# Project_Zero.net
KiCad netlist of a schematic drawn in EasyEDA Pro
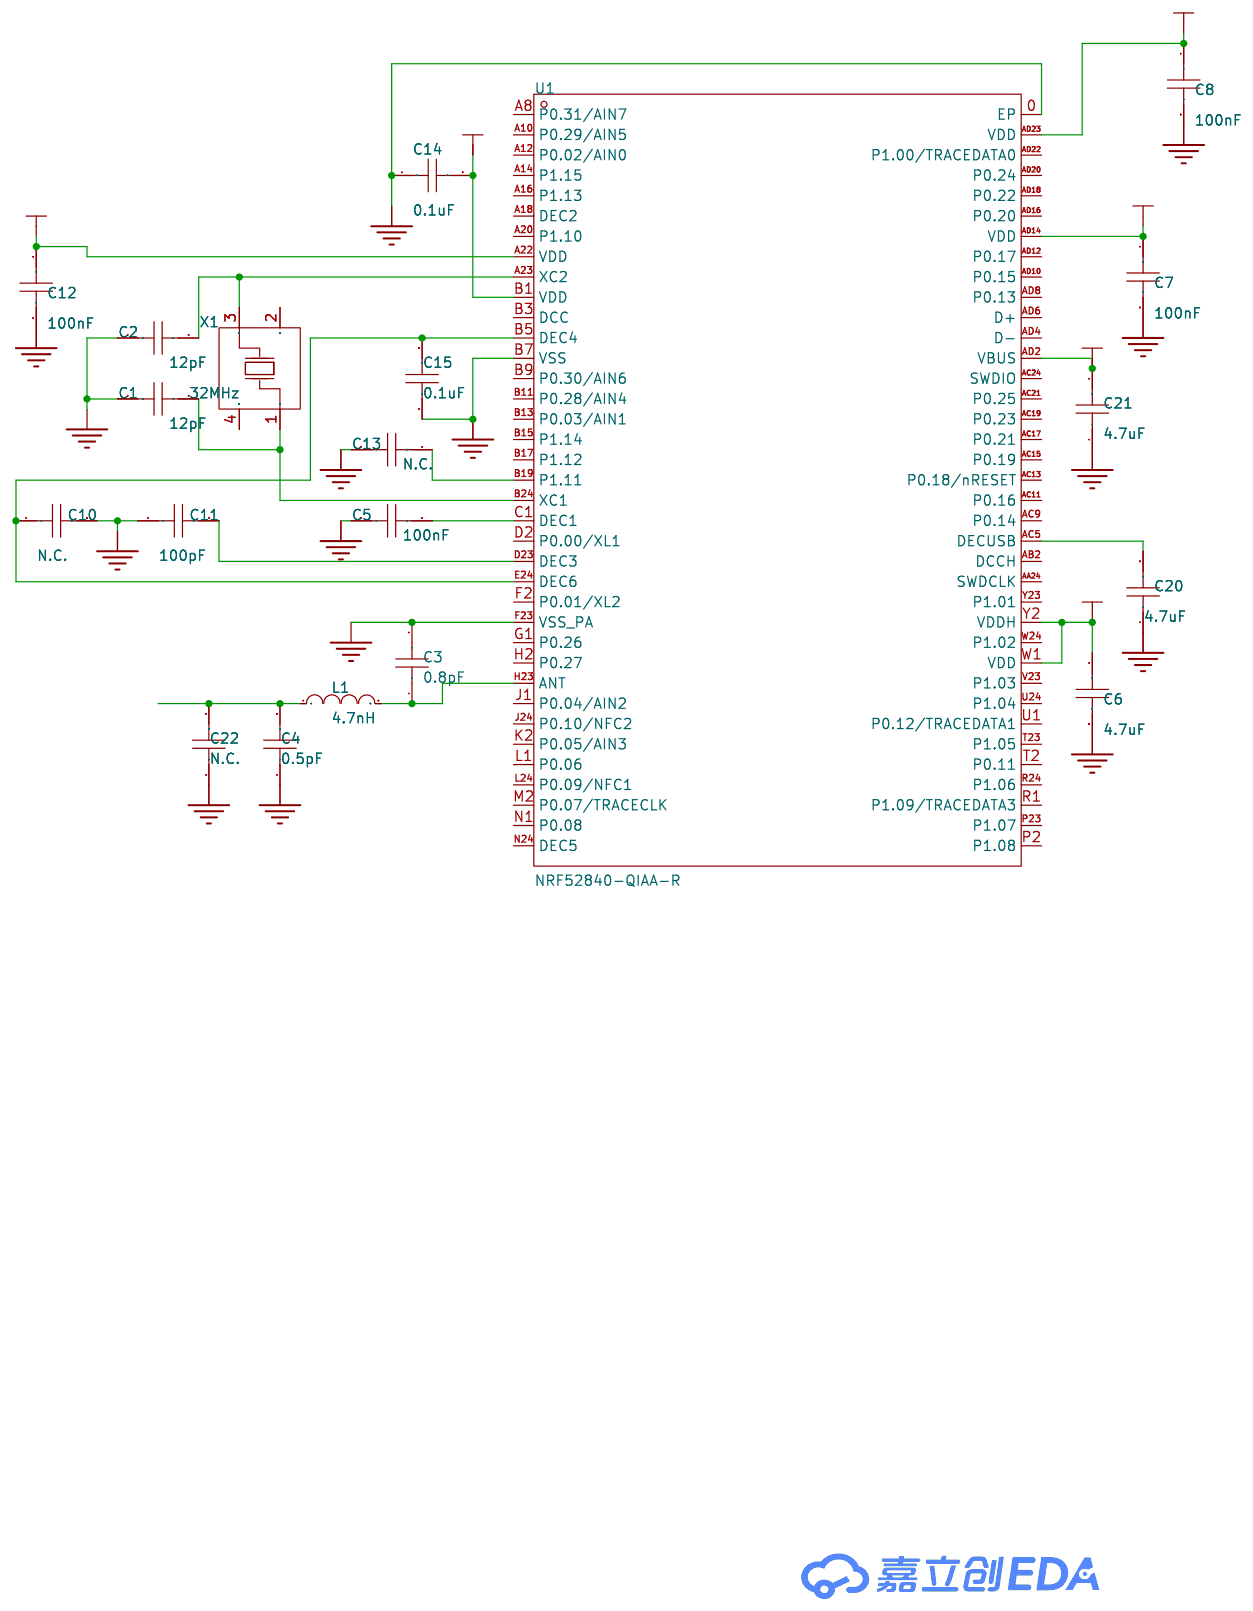
[diagram p0: schematic sheet]

(export (version "E")
  (design (tool "Eeschema 10.0.6"))
  (components
    (comp (ref "C1")
      (value "12pF")
      (footprint "easyedapro:C0603")
      (libsource (lib "easyedapro") (part "CapAcitance"))
    )
    (comp (ref "C2")
      (value "12pF")
      (footprint "easyedapro:C0603")
      (libsource (lib "easyedapro") (part "CapAcitance"))
    )
    (comp (ref "C3")
      (value "0.8pF")
      (footprint "easyedapro:C0603")
      (libsource (lib "easyedapro") (part "CapAcitance"))
    )
    (comp (ref "C4")
      (value "0.5pF")
      (footprint "easyedapro:C0603")
      (libsource (lib "easyedapro") (part "CapAcitance"))
    )
    (comp (ref "C5")
      (value "100nF")
      (footprint "easyedapro:C0603")
      (libsource (lib "easyedapro") (part "CapAcitance"))
    )
    (comp (ref "C6")
      (value "4.7uF")
      (footprint "easyedapro:C0603")
      (libsource (lib "easyedapro") (part "CapAcitance"))
    )
    (comp (ref "C7")
      (value "100nF")
      (footprint "easyedapro:C0603")
      (libsource (lib "easyedapro") (part "CapAcitance"))
    )
    (comp (ref "C8")
      (value "100nF")
      (footprint "easyedapro:C0603")
      (libsource (lib "easyedapro") (part "CapAcitance"))
    )
    (comp (ref "C10")
      (value "N.C.")
      (footprint "easyedapro:C0603")
      (libsource (lib "easyedapro") (part "CapAcitance"))
    )
    (comp (ref "C11")
      (value "100pF")
      (footprint "easyedapro:C0603")
      (libsource (lib "easyedapro") (part "CapAcitance"))
    )
    (comp (ref "C12")
      (value "100nF")
      (footprint "easyedapro:C0603")
      (libsource (lib "easyedapro") (part "CapAcitance"))
    )
    (comp (ref "C13")
      (value "N.C.")
      (footprint "easyedapro:C0603")
      (libsource (lib "easyedapro") (part "CapAcitance"))
    )
    (comp (ref "C14")
      (value "0.1uF")
      (footprint "easyedapro:C0603")
      (libsource (lib "easyedapro") (part "CapAcitance"))
    )
    (comp (ref "C15")
      (value "0.1uF")
      (footprint "easyedapro:C0603")
      (libsource (lib "easyedapro") (part "CapAcitance"))
    )
    (comp (ref "C20")
      (value "4.7uF")
      (footprint "easyedapro:C0603")
      (libsource (lib "easyedapro") (part "CapAcitance"))
    )
    (comp (ref "C21")
      (value "4.7uF")
      (footprint "easyedapro:C0603")
      (libsource (lib "easyedapro") (part "CapAcitance"))
    )
    (comp (ref "C22")
      (value "N.C.")
      (footprint "easyedapro:C0603")
      (libsource (lib "easyedapro") (part "CapAcitance"))
    )
    (comp (ref "L1")
      (value "4.7nH")
      (footprint "easyedapro:L0603")
      (libsource (lib "easyedapro") (part "SDFL1608S100KTF"))
    )
    (comp (ref "U1")
      (value "NRF52840-QIAA-R")
      (footprint "easyedapro:AQFN-73_L7.0-W7.0-P0.50-BL-EP4.8")
      (fields (field (name "Manufacturer") "NORDIC"))
      (libsource (lib "easyedapro") (part "NRF52840-QIAA-R"))
    )
    (comp (ref "X1")
      (value "32MHz")
      (footprint "easyedapro:CRYSTAL-SMD_4P-L3.2-W2.5-BL")
      (description "晶振类型:贴片晶振;频率:32MHz;常温频差:±10ppm;外接负载电容:12pF;频率稳定度(全温):±20ppm;")
      (fields (field (name "Manufacturer Part") "X322532MOB4SI") (field (name "Manufacturer") "YXC(扬兴晶振)"))
      (libsource (lib "easyedapro") (part "X322532MOB4SI"))
    )
  )
  (nets
    (net (code "1") (name "GND") (class "Default")
      (node (ref "C1") (pin "1") (pinfunction "1_1") (pintype "input"))
      (node (ref "C10") (pin "2") (pinfunction "2_2") (pintype "input"))
      (node (ref "C11") (pin "1") (pinfunction "1_1") (pintype "input"))
      (node (ref "C12") (pin "2") (pinfunction "2_2") (pintype "input"))
      (node (ref "C13") (pin "1") (pinfunction "1_1") (pintype "input"))
      (node (ref "C14") (pin "1") (pinfunction "1_1") (pintype "input"))
      (node (ref "C15") (pin "1") (pinfunction "1_1") (pintype "input"))
      (node (ref "C2") (pin "1") (pinfunction "1_1") (pintype "input"))
      (node (ref "C20") (pin "1") (pinfunction "1_1") (pintype "input"))
      (node (ref "C21") (pin "1") (pinfunction "1_1") (pintype "input"))
      (node (ref "C22") (pin "1") (pinfunction "1_1") (pintype "input"))
      (node (ref "C3") (pin "2") (pinfunction "2_2") (pintype "input"))
      (node (ref "C4") (pin "1") (pinfunction "1_1") (pintype "input"))
      (node (ref "C5") (pin "1") (pinfunction "1_1") (pintype "input"))
      (node (ref "C6") (pin "2") (pinfunction "2_2") (pintype "input"))
      (node (ref "C7") (pin "2") (pinfunction "2_2") (pintype "input"))
      (node (ref "C8") (pin "2") (pinfunction "2_2") (pintype "input"))
      (node (ref "U1") (pin "0") (pinfunction "EP_0") (pintype "unspecified"))
      (node (ref "U1") (pin "B7") (pinfunction "VSS_B7") (pintype "unspecified"))
      (node (ref "U1") (pin "F23") (pinfunction "VSS_PA_F23") (pintype "unspecified"))
    )
    (net (code "2") (name "Net-(C22-Pad2)") (class "Default")
      (node (ref "C22") (pin "2") (pinfunction "2_2") (pintype "input"))
      (node (ref "C4") (pin "2") (pinfunction "2_2") (pintype "input"))
      (node (ref "L1") (pin "1") (pinfunction "1_1") (pintype "unspecified"))
    )
    (net (code "3") (name "Net-(U1-ANT)") (class "Default")
      (node (ref "C3") (pin "1") (pinfunction "1_1") (pintype "input"))
      (node (ref "L1") (pin "2") (pinfunction "2_2") (pintype "unspecified"))
      (node (ref "U1") (pin "H23") (pinfunction "ANT_H23") (pintype "unspecified"))
    )
    (net (code "4") (name "Net-(U1-DEC1)") (class "Default")
      (node (ref "C5") (pin "2") (pinfunction "2_2") (pintype "input"))
      (node (ref "U1") (pin "C1") (pinfunction "DEC1_C1") (pintype "unspecified"))
    )
    (net (code "5") (name "Net-(U1-DEC3)") (class "Default")
      (node (ref "C11") (pin "2") (pinfunction "2_2") (pintype "input"))
      (node (ref "U1") (pin "D23") (pinfunction "DEC3_D23") (pintype "unspecified"))
    )
    (net (code "6") (name "Net-(U1-DEC4)") (class "Default")
      (node (ref "C10") (pin "1") (pinfunction "1_1") (pintype "input"))
      (node (ref "C15") (pin "2") (pinfunction "2_2") (pintype "input"))
      (node (ref "U1") (pin "B5") (pinfunction "DEC4_B5") (pintype "unspecified"))
      (node (ref "U1") (pin "E24") (pinfunction "DEC6_E24") (pintype "unspecified"))
    )
    (net (code "7") (name "Net-(U1-DECUSB)") (class "Default")
      (node (ref "C20") (pin "2") (pinfunction "2_2") (pintype "input"))
      (node (ref "U1") (pin "AC5") (pinfunction "DECUSB_AC5") (pintype "unspecified"))
    )
    (net (code "8") (name "Net-(U1-P1.11)") (class "Default")
      (node (ref "C13") (pin "2") (pinfunction "2_2") (pintype "input"))
      (node (ref "U1") (pin "B19") (pinfunction "P1.11_B19") (pintype "unspecified"))
    )
    (net (code "9") (name "Net-(U1-XC1)") (class "Default")
      (node (ref "C1") (pin "2") (pinfunction "2_2") (pintype "input"))
      (node (ref "U1") (pin "B24") (pinfunction "XC1_B24") (pintype "unspecified"))
      (node (ref "X1") (pin "1") (pinfunction "OSC1_1") (pintype "unspecified"))
    )
    (net (code "10") (name "Net-(U1-XC2)") (class "Default")
      (node (ref "C2") (pin "2") (pinfunction "2_2") (pintype "input"))
      (node (ref "U1") (pin "A23") (pinfunction "XC2_A23") (pintype "unspecified"))
      (node (ref "X1") (pin "3") (pinfunction "OSC2_3") (pintype "unspecified"))
    )
    (net (code "11") (name "VBUS") (class "Default")
      (node (ref "C21") (pin "2") (pinfunction "2_2") (pintype "input"))
      (node (ref "U1") (pin "AD2") (pinfunction "VBUS_AD2") (pintype "unspecified"))
    )
    (net (code "12") (name "VDD") (class "Default")
      (node (ref "C12") (pin "1") (pinfunction "1_1") (pintype "input"))
      (node (ref "C14") (pin "2") (pinfunction "2_2") (pintype "input"))
      (node (ref "C6") (pin "1") (pinfunction "1_1") (pintype "input"))
      (node (ref "C7") (pin "1") (pinfunction "1_1") (pintype "input"))
      (node (ref "C8") (pin "1") (pinfunction "1_1") (pintype "input"))
      (node (ref "U1") (pin "A22") (pinfunction "VDD_A22") (pintype "unspecified"))
      (node (ref "U1") (pin "AD14") (pinfunction "VDD_AD14") (pintype "unspecified"))
      (node (ref "U1") (pin "AD23") (pinfunction "VDD_AD23") (pintype "unspecified"))
      (node (ref "U1") (pin "B1") (pinfunction "VDD_B1") (pintype "unspecified"))
      (node (ref "U1") (pin "W1") (pinfunction "VDD_W1") (pintype "unspecified"))
      (node (ref "U1") (pin "Y2") (pinfunction "VDDH_Y2") (pintype "unspecified"))
    )
    (net (code "13") (name "unconnected-(U1-D+-PadAD6)") (class "Default")
      (node (ref "U1") (pin "AD6") (pinfunction "D+_AD6") (pintype "unspecified"))
    )
    (net (code "14") (name "unconnected-(U1-D--PadAD4)") (class "Default")
      (node (ref "U1") (pin "AD4") (pinfunction "D-_AD4") (pintype "unspecified"))
    )
    (net (code "15") (name "unconnected-(U1-DCC-PadB3)") (class "Default")
      (node (ref "U1") (pin "B3") (pinfunction "DCC_B3") (pintype "unspecified"))
    )
    (net (code "16") (name "unconnected-(U1-DCCH-PadAB2)") (class "Default")
      (node (ref "U1") (pin "AB2") (pinfunction "DCCH_AB2") (pintype "unspecified"))
    )
    (net (code "17") (name "unconnected-(U1-DEC2-PadA18)") (class "Default")
      (node (ref "U1") (pin "A18") (pinfunction "DEC2_A18") (pintype "unspecified"))
    )
    (net (code "18") (name "unconnected-(U1-DEC5-PadN24)") (class "Default")
      (node (ref "U1") (pin "N24") (pinfunction "DEC5_N24") (pintype "unspecified"))
    )
    (net (code "19") (name "unconnected-(U1-P0.00{slash}XL1-PadD2)") (class "Default")
      (node (ref "U1") (pin "D2") (pinfunction "P0.00/XL1_D2") (pintype "unspecified"))
    )
    (net (code "20") (name "unconnected-(U1-P0.01{slash}XL2-PadF2)") (class "Default")
      (node (ref "U1") (pin "F2") (pinfunction "P0.01/XL2_F2") (pintype "unspecified"))
    )
    (net (code "21") (name "unconnected-(U1-P0.02{slash}AIN0-PadA12)") (class "Default")
      (node (ref "U1") (pin "A12") (pinfunction "P0.02/AIN0_A12") (pintype "unspecified"))
    )
    (net (code "22") (name "unconnected-(U1-P0.03{slash}AIN1-PadB13)") (class "Default")
      (node (ref "U1") (pin "B13") (pinfunction "P0.03/AIN1_B13") (pintype "unspecified"))
    )
    (net (code "23") (name "unconnected-(U1-P0.04{slash}AIN2-PadJ1)") (class "Default")
      (node (ref "U1") (pin "J1") (pinfunction "P0.04/AIN2_J1") (pintype "unspecified"))
    )
    (net (code "24") (name "unconnected-(U1-P0.05{slash}AIN3-PadK2)") (class "Default")
      (node (ref "U1") (pin "K2") (pinfunction "P0.05/AIN3_K2") (pintype "unspecified"))
    )
    (net (code "25") (name "unconnected-(U1-P0.06-PadL1)") (class "Default")
      (node (ref "U1") (pin "L1") (pinfunction "P0.06_L1") (pintype "unspecified"))
    )
    (net (code "26") (name "unconnected-(U1-P0.07{slash}TRACECLK-PadM2)") (class "Default")
      (node (ref "U1") (pin "M2") (pinfunction "P0.07/TRACECLK_M2") (pintype "unspecified"))
    )
    (net (code "27") (name "unconnected-(U1-P0.08-PadN1)") (class "Default")
      (node (ref "U1") (pin "N1") (pinfunction "P0.08_N1") (pintype "unspecified"))
    )
    (net (code "28") (name "unconnected-(U1-P0.09{slash}NFC1-PadL24)") (class "Default")
      (node (ref "U1") (pin "L24") (pinfunction "P0.09/NFC1_L24") (pintype "unspecified"))
    )
    (net (code "29") (name "unconnected-(U1-P0.10{slash}NFC2-PadJ24)") (class "Default")
      (node (ref "U1") (pin "J24") (pinfunction "P0.10/NFC2_J24") (pintype "unspecified"))
    )
    (net (code "30") (name "unconnected-(U1-P0.11-PadT2)") (class "Default")
      (node (ref "U1") (pin "T2") (pinfunction "P0.11_T2") (pintype "unspecified"))
    )
    (net (code "31") (name "unconnected-(U1-P0.12{slash}TRACEDATA1-PadU1)") (class "Default")
      (node (ref "U1") (pin "U1") (pinfunction "P0.12/TRACEDATA1_U1") (pintype "unspecified"))
    )
    (net (code "32") (name "unconnected-(U1-P0.13-PadAD8)") (class "Default")
      (node (ref "U1") (pin "AD8") (pinfunction "P0.13_AD8") (pintype "unspecified"))
    )
    (net (code "33") (name "unconnected-(U1-P0.14-PadAC9)") (class "Default")
      (node (ref "U1") (pin "AC9") (pinfunction "P0.14_AC9") (pintype "unspecified"))
    )
    (net (code "34") (name "unconnected-(U1-P0.15-PadAD10)") (class "Default")
      (node (ref "U1") (pin "AD10") (pinfunction "P0.15_AD10") (pintype "unspecified"))
    )
    (net (code "35") (name "unconnected-(U1-P0.16-PadAC11)") (class "Default")
      (node (ref "U1") (pin "AC11") (pinfunction "P0.16_AC11") (pintype "unspecified"))
    )
    (net (code "36") (name "unconnected-(U1-P0.17-PadAD12)") (class "Default")
      (node (ref "U1") (pin "AD12") (pinfunction "P0.17_AD12") (pintype "unspecified"))
    )
    (net (code "37") (name "unconnected-(U1-P0.18{slash}nRESET-PadAC13)") (class "Default")
      (node (ref "U1") (pin "AC13") (pinfunction "P0.18/nRESET_AC13") (pintype "unspecified"))
    )
    (net (code "38") (name "unconnected-(U1-P0.19-PadAC15)") (class "Default")
      (node (ref "U1") (pin "AC15") (pinfunction "P0.19_AC15") (pintype "unspecified"))
    )
    (net (code "39") (name "unconnected-(U1-P0.20-PadAD16)") (class "Default")
      (node (ref "U1") (pin "AD16") (pinfunction "P0.20_AD16") (pintype "unspecified"))
    )
    (net (code "40") (name "unconnected-(U1-P0.21-PadAC17)") (class "Default")
      (node (ref "U1") (pin "AC17") (pinfunction "P0.21_AC17") (pintype "unspecified"))
    )
    (net (code "41") (name "unconnected-(U1-P0.22-PadAD18)") (class "Default")
      (node (ref "U1") (pin "AD18") (pinfunction "P0.22_AD18") (pintype "unspecified"))
    )
    (net (code "42") (name "unconnected-(U1-P0.23-PadAC19)") (class "Default")
      (node (ref "U1") (pin "AC19") (pinfunction "P0.23_AC19") (pintype "unspecified"))
    )
    (net (code "43") (name "unconnected-(U1-P0.24-PadAD20)") (class "Default")
      (node (ref "U1") (pin "AD20") (pinfunction "P0.24_AD20") (pintype "unspecified"))
    )
    (net (code "44") (name "unconnected-(U1-P0.25-PadAC21)") (class "Default")
      (node (ref "U1") (pin "AC21") (pinfunction "P0.25_AC21") (pintype "unspecified"))
    )
    (net (code "45") (name "unconnected-(U1-P0.26-PadG1)") (class "Default")
      (node (ref "U1") (pin "G1") (pinfunction "P0.26_G1") (pintype "unspecified"))
    )
    (net (code "46") (name "unconnected-(U1-P0.27-PadH2)") (class "Default")
      (node (ref "U1") (pin "H2") (pinfunction "P0.27_H2") (pintype "unspecified"))
    )
    (net (code "47") (name "unconnected-(U1-P0.28{slash}AIN4-PadB11)") (class "Default")
      (node (ref "U1") (pin "B11") (pinfunction "P0.28/AIN4_B11") (pintype "unspecified"))
    )
    (net (code "48") (name "unconnected-(U1-P0.29{slash}AIN5-PadA10)") (class "Default")
      (node (ref "U1") (pin "A10") (pinfunction "P0.29/AIN5_A10") (pintype "unspecified"))
    )
    (net (code "49") (name "unconnected-(U1-P0.30{slash}AIN6-PadB9)") (class "Default")
      (node (ref "U1") (pin "B9") (pinfunction "P0.30/AIN6_B9") (pintype "unspecified"))
    )
    (net (code "50") (name "unconnected-(U1-P0.31{slash}AIN7-PadA8)") (class "Default")
      (node (ref "U1") (pin "A8") (pinfunction "P0.31/AIN7_A8") (pintype "unspecified"))
    )
    (net (code "51") (name "unconnected-(U1-P1.00{slash}TRACEDATA0-PadAD22)") (class "Default")
      (node (ref "U1") (pin "AD22") (pinfunction "P1.00/TRACEDATA0_AD22") (pintype "unspecified"))
    )
    (net (code "52") (name "unconnected-(U1-P1.01-PadY23)") (class "Default")
      (node (ref "U1") (pin "Y23") (pinfunction "P1.01_Y23") (pintype "unspecified"))
    )
    (net (code "53") (name "unconnected-(U1-P1.02-PadW24)") (class "Default")
      (node (ref "U1") (pin "W24") (pinfunction "P1.02_W24") (pintype "unspecified"))
    )
    (net (code "54") (name "unconnected-(U1-P1.03-PadV23)") (class "Default")
      (node (ref "U1") (pin "V23") (pinfunction "P1.03_V23") (pintype "unspecified"))
    )
    (net (code "55") (name "unconnected-(U1-P1.04-PadU24)") (class "Default")
      (node (ref "U1") (pin "U24") (pinfunction "P1.04_U24") (pintype "unspecified"))
    )
    (net (code "56") (name "unconnected-(U1-P1.05-PadT23)") (class "Default")
      (node (ref "U1") (pin "T23") (pinfunction "P1.05_T23") (pintype "unspecified"))
    )
    (net (code "57") (name "unconnected-(U1-P1.06-PadR24)") (class "Default")
      (node (ref "U1") (pin "R24") (pinfunction "P1.06_R24") (pintype "unspecified"))
    )
    (net (code "58") (name "unconnected-(U1-P1.07-PadP23)") (class "Default")
      (node (ref "U1") (pin "P23") (pinfunction "P1.07_P23") (pintype "unspecified"))
    )
    (net (code "59") (name "unconnected-(U1-P1.08-PadP2)") (class "Default")
      (node (ref "U1") (pin "P2") (pinfunction "P1.08_P2") (pintype "unspecified"))
    )
    (net (code "60") (name "unconnected-(U1-P1.09{slash}TRACEDATA3-PadR1)") (class "Default")
      (node (ref "U1") (pin "R1") (pinfunction "P1.09/TRACEDATA3_R1") (pintype "unspecified"))
    )
    (net (code "61") (name "unconnected-(U1-P1.10-PadA20)") (class "Default")
      (node (ref "U1") (pin "A20") (pinfunction "P1.10_A20") (pintype "unspecified"))
    )
    (net (code "62") (name "unconnected-(U1-P1.12-PadB17)") (class "Default")
      (node (ref "U1") (pin "B17") (pinfunction "P1.12_B17") (pintype "unspecified"))
    )
    (net (code "63") (name "unconnected-(U1-P1.13-PadA16)") (class "Default")
      (node (ref "U1") (pin "A16") (pinfunction "P1.13_A16") (pintype "unspecified"))
    )
    (net (code "64") (name "unconnected-(U1-P1.14-PadB15)") (class "Default")
      (node (ref "U1") (pin "B15") (pinfunction "P1.14_B15") (pintype "unspecified"))
    )
    (net (code "65") (name "unconnected-(U1-P1.15-PadA14)") (class "Default")
      (node (ref "U1") (pin "A14") (pinfunction "P1.15_A14") (pintype "unspecified"))
    )
    (net (code "66") (name "unconnected-(U1-SWDCLK-PadAA24)") (class "Default")
      (node (ref "U1") (pin "AA24") (pinfunction "SWDCLK_AA24") (pintype "unspecified"))
    )
    (net (code "67") (name "unconnected-(U1-SWDIO-PadAC24)") (class "Default")
      (node (ref "U1") (pin "AC24") (pinfunction "SWDIO_AC24") (pintype "unspecified"))
    )
    (net (code "68") (name "unconnected-(X1-GND-Pad2)") (class "Default")
      (node (ref "X1") (pin "2") (pinfunction "GND_2") (pintype "unspecified"))
    )
    (net (code "69") (name "unconnected-(X1-GND-Pad4)") (class "Default")
      (node (ref "X1") (pin "4") (pinfunction "GND_4") (pintype "unspecified"))
    )
  )
)
